# PhotoInterruptor.net
KiCad netlist of a schematic drawn in EAGLE
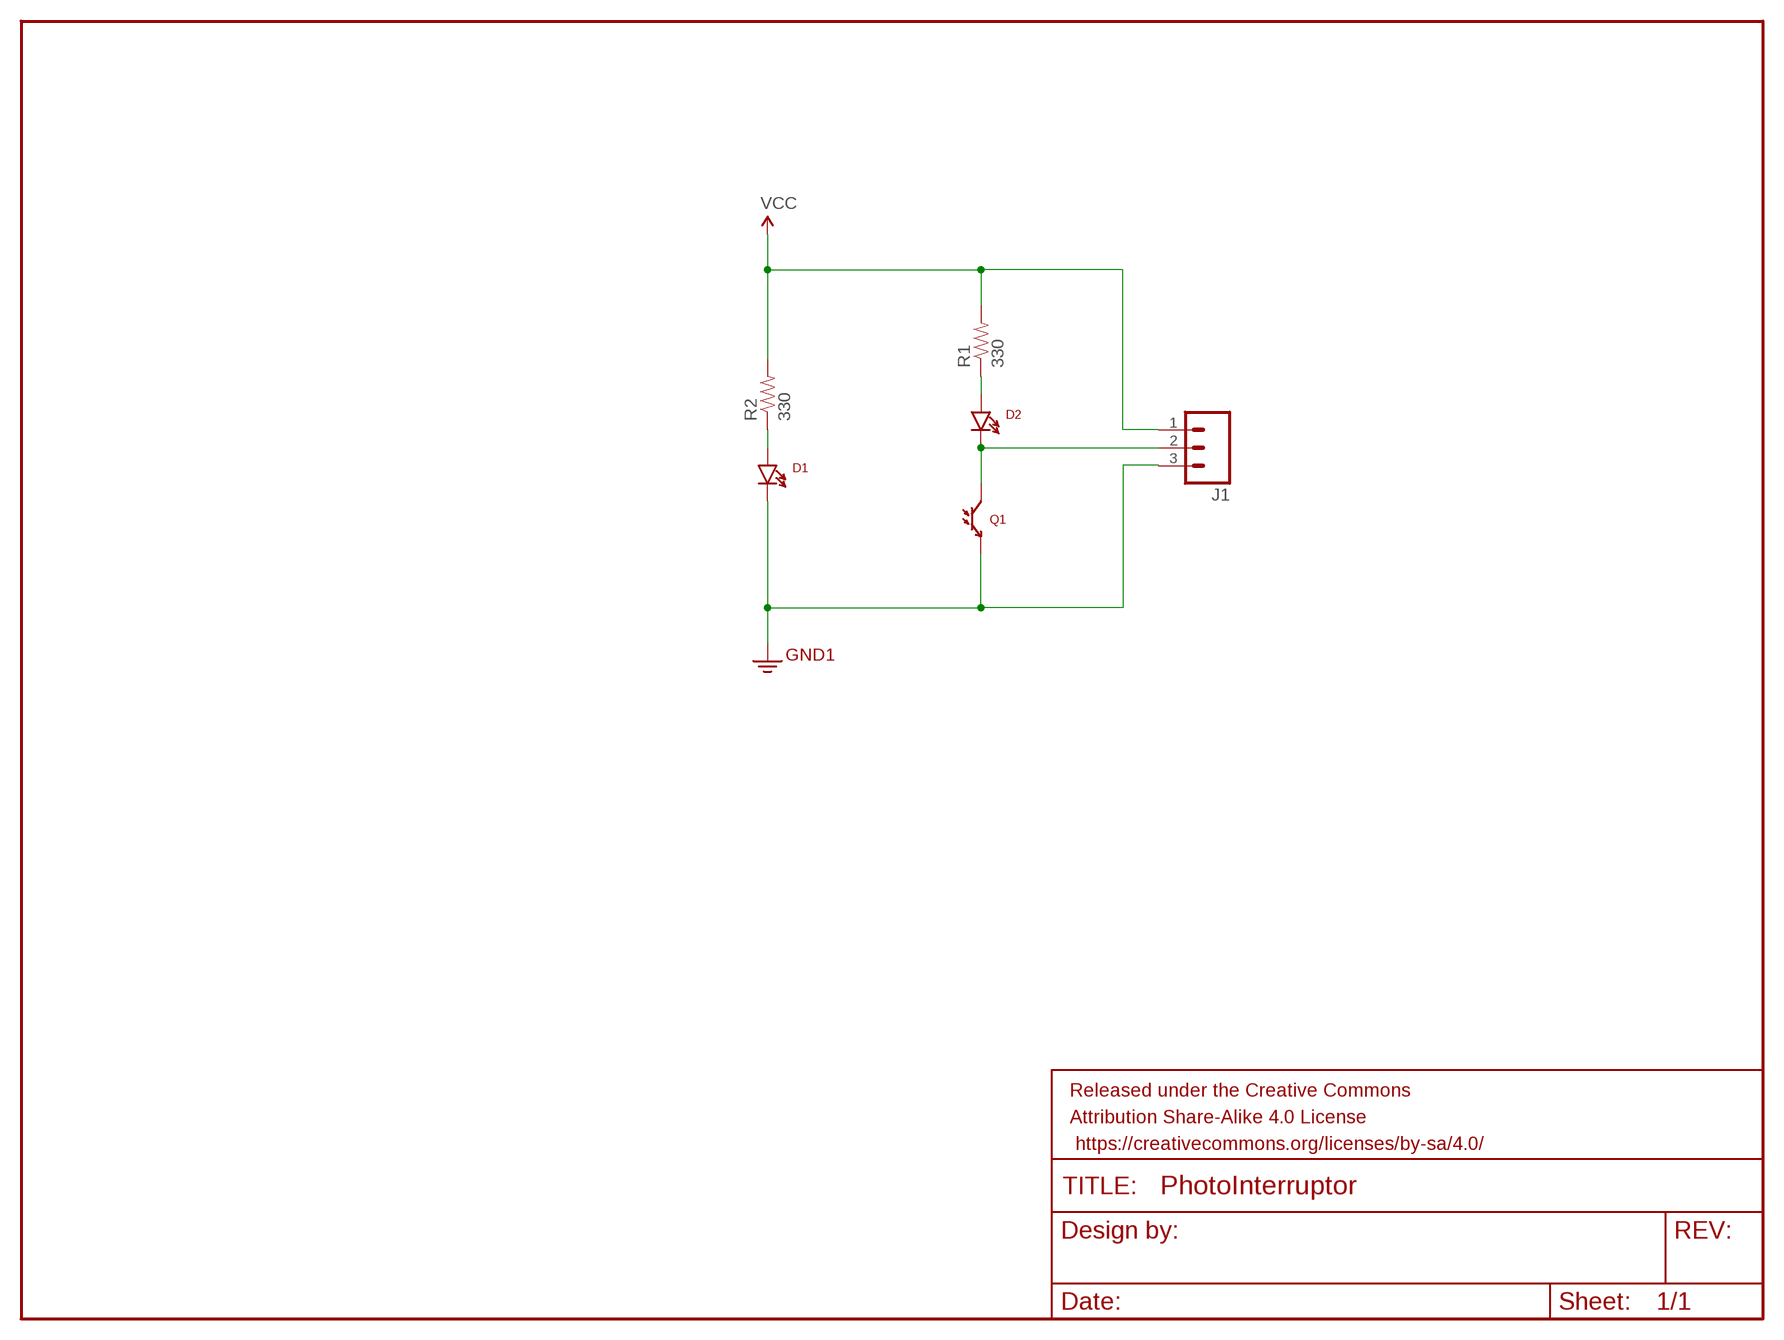
[diagram p0: schematic, sheet 1]

(export (version "E")
  (design (tool "Eeschema 10.0.6"))
  (components
    (comp (ref "D1")
      (value "LTE-302")
      (footprint "eagle-import:LTE-302")
      (libsource (lib "eagle-import") (part "LTE-302"))
    )
    (comp (ref "D2")
      (value "LTE-302")
      (footprint "eagle-import:LTE-302")
      (libsource (lib "eagle-import") (part "LTE-302"))
    )
    (comp (ref "FRAME1")
      (value "FRAME-LETTERNO_PACKAGE")
      (footprint "eagle-import:DUMMY")
      (fields (field (name "DESIGNER") "Nobody"))
      (libsource (lib "eagle-import") (part "FRAME-LETTERNO_PACKAGE"))
    )
    (comp (ref "J1")
      (value "M03POGO_PIN_HOLES_ONLY")
      (footprint "eagle-import:1X03_PP_HOLES_ONLY")
      (libsource (lib "eagle-import") (part "M03POGO_PIN_HOLES_ONLY"))
    )
    (comp (ref "Q1")
      (value "LTR-301")
      (footprint "eagle-import:LTR-301")
      (libsource (lib "eagle-import") (part "LTR-301"))
    )
    (comp (ref "R1")
      (value "330")
      (footprint "eagle-import:AXIAL-0.3")
      (libsource (lib "eagle-import") (part "10KOHM-1/4W-1%(PTH)HORIZ"))
    )
    (comp (ref "R2")
      (value "330")
      (footprint "eagle-import:AXIAL-0.3")
      (libsource (lib "eagle-import") (part "10KOHM-1/4W-1%(PTH)HORIZ"))
    )
  )
  (nets
    (net (code "1") (name "GND2") (class "Default")
      (node (ref "D1") (pin "C") (pinfunction "C_C") (pintype "bidirectional"))
      (node (ref "J1") (pin "3") (pinfunction "3_3") (pintype "passive"))
      (node (ref "Q1") (pin "E") (pinfunction "E_E") (pintype "bidirectional"))
    )
    (net (code "2") (name "Net-(D2-PadC)") (class "Default")
      (node (ref "D2") (pin "C") (pinfunction "C_C") (pintype "bidirectional"))
      (node (ref "J1") (pin "2") (pinfunction "2_2") (pintype "passive"))
      (node (ref "Q1") (pin "C") (pinfunction "C_C") (pintype "bidirectional"))
    )
    (net (code "3") (name "Net-(R1-1)") (class "Default")
      (node (ref "D2") (pin "A") (pinfunction "A_A") (pintype "bidirectional"))
      (node (ref "R1") (pin "P$1") (pinfunction "1_P$1") (pintype "passive"))
    )
    (net (code "4") (name "Net-(R2-1)") (class "Default")
      (node (ref "D1") (pin "A") (pinfunction "A_A") (pintype "bidirectional"))
      (node (ref "R2") (pin "P$1") (pinfunction "1_P$1") (pintype "passive"))
    )
    (net (code "5") (name "VCC") (class "Default")
      (node (ref "J1") (pin "1") (pinfunction "1_1") (pintype "passive"))
      (node (ref "R1") (pin "P$2") (pinfunction "2_P$2") (pintype "passive"))
      (node (ref "R2") (pin "P$2") (pinfunction "2_P$2") (pintype "passive"))
    )
  )
)
